# Valves.net
KiCad netlist of a schematic drawn in Altium Designer
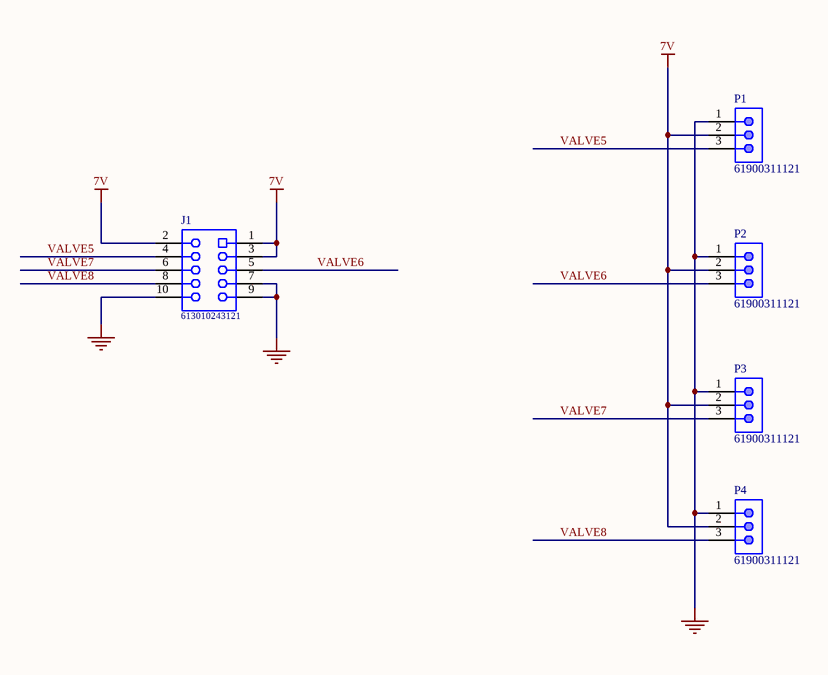
[diagram p0: Valves.SchDoc]

(export (version "E")
  (design (tool "Eeschema 10.0.6"))
  (components
    (comp (ref "J1")
      (value "613010243121")
      (footprint "613010243121")
      (description "WR-PHD Socket Header, THT, pitch 2.54mm, Dual Row, Angled, 10p")
      (fields (field (name "MANUFACTURER") "Wurth Elektronik"))
      (libsource (lib "Altium_WR-PHD (rev22a)") (part "613010243121"))
    )
    (comp (ref "P1")
      (value "61900311121")
      (footprint "61900311121")
      (description "WR-WTB THT Male Vertical Locking Header, pitch 2.54mm, 3p")
      (fields (field (name "PUBLISHER") "Wurth Elektronik"))
      (libsource (lib "Altium_WR-WTB (rev20a)") (part "61900311121"))
    )
    (comp (ref "P2")
      (value "61900311121")
      (footprint "61900311121")
      (description "WR-WTB THT Male Vertical Locking Header, pitch 2.54mm, 3p")
      (fields (field (name "PUBLISHER") "Wurth Elektronik"))
      (libsource (lib "Altium_WR-WTB (rev20a)") (part "61900311121"))
    )
    (comp (ref "P3")
      (value "61900311121")
      (footprint "61900311121")
      (description "WR-WTB THT Male Vertical Locking Header, pitch 2.54mm, 3p")
      (fields (field (name "PUBLISHER") "Wurth Elektronik"))
      (libsource (lib "Altium_WR-WTB (rev20a)") (part "61900311121"))
    )
    (comp (ref "P4")
      (value "61900311121")
      (footprint "61900311121")
      (description "WR-WTB THT Male Vertical Locking Header, pitch 2.54mm, 3p")
      (fields (field (name "PUBLISHER") "Wurth Elektronik"))
      (libsource (lib "Altium_WR-WTB (rev20a)") (part "61900311121"))
    )
  )
  (nets
    (net (code "1") (name "/VALVE5") (class "Default")
      (node (ref "J1") (pin "4") (pinfunction "4_4") (pintype "passive"))
      (node (ref "P1") (pin "3") (pinfunction "3_3") (pintype "passive"))
    )
    (net (code "2") (name "/VALVE6") (class "Default")
      (node (ref "J1") (pin "5") (pinfunction "5_5") (pintype "passive"))
      (node (ref "P2") (pin "3") (pinfunction "3_3") (pintype "passive"))
    )
    (net (code "3") (name "/VALVE7") (class "Default")
      (node (ref "J1") (pin "6") (pinfunction "6_6") (pintype "passive"))
      (node (ref "P3") (pin "3") (pinfunction "3_3") (pintype "passive"))
    )
    (net (code "4") (name "/VALVE8") (class "Default")
      (node (ref "J1") (pin "8") (pinfunction "8_8") (pintype "passive"))
      (node (ref "P4") (pin "3") (pinfunction "3_3") (pintype "passive"))
    )
    (net (code "5") (name "7V") (class "Default")
      (node (ref "J1") (pin "1") (pinfunction "1_1") (pintype "passive"))
      (node (ref "J1") (pin "2") (pinfunction "2_2") (pintype "passive"))
      (node (ref "J1") (pin "3") (pinfunction "3_3") (pintype "passive"))
      (node (ref "P1") (pin "2") (pinfunction "2_2") (pintype "passive"))
      (node (ref "P2") (pin "2") (pinfunction "2_2") (pintype "passive"))
      (node (ref "P3") (pin "2") (pinfunction "2_2") (pintype "passive"))
      (node (ref "P4") (pin "2") (pinfunction "2_2") (pintype "passive"))
    )
    (net (code "6") (name "GND") (class "Default")
      (node (ref "J1") (pin "10") (pinfunction "10_10") (pintype "passive"))
      (node (ref "J1") (pin "7") (pinfunction "7_7") (pintype "passive"))
      (node (ref "J1") (pin "9") (pinfunction "9_9") (pintype "passive"))
      (node (ref "P1") (pin "1") (pinfunction "1_1") (pintype "passive"))
      (node (ref "P2") (pin "1") (pinfunction "1_1") (pintype "passive"))
      (node (ref "P3") (pin "1") (pinfunction "1_1") (pintype "passive"))
      (node (ref "P4") (pin "1") (pinfunction "1_1") (pintype "passive"))
    )
  )
)
